# Power.net
KiCad netlist of a schematic drawn in Altium Designer
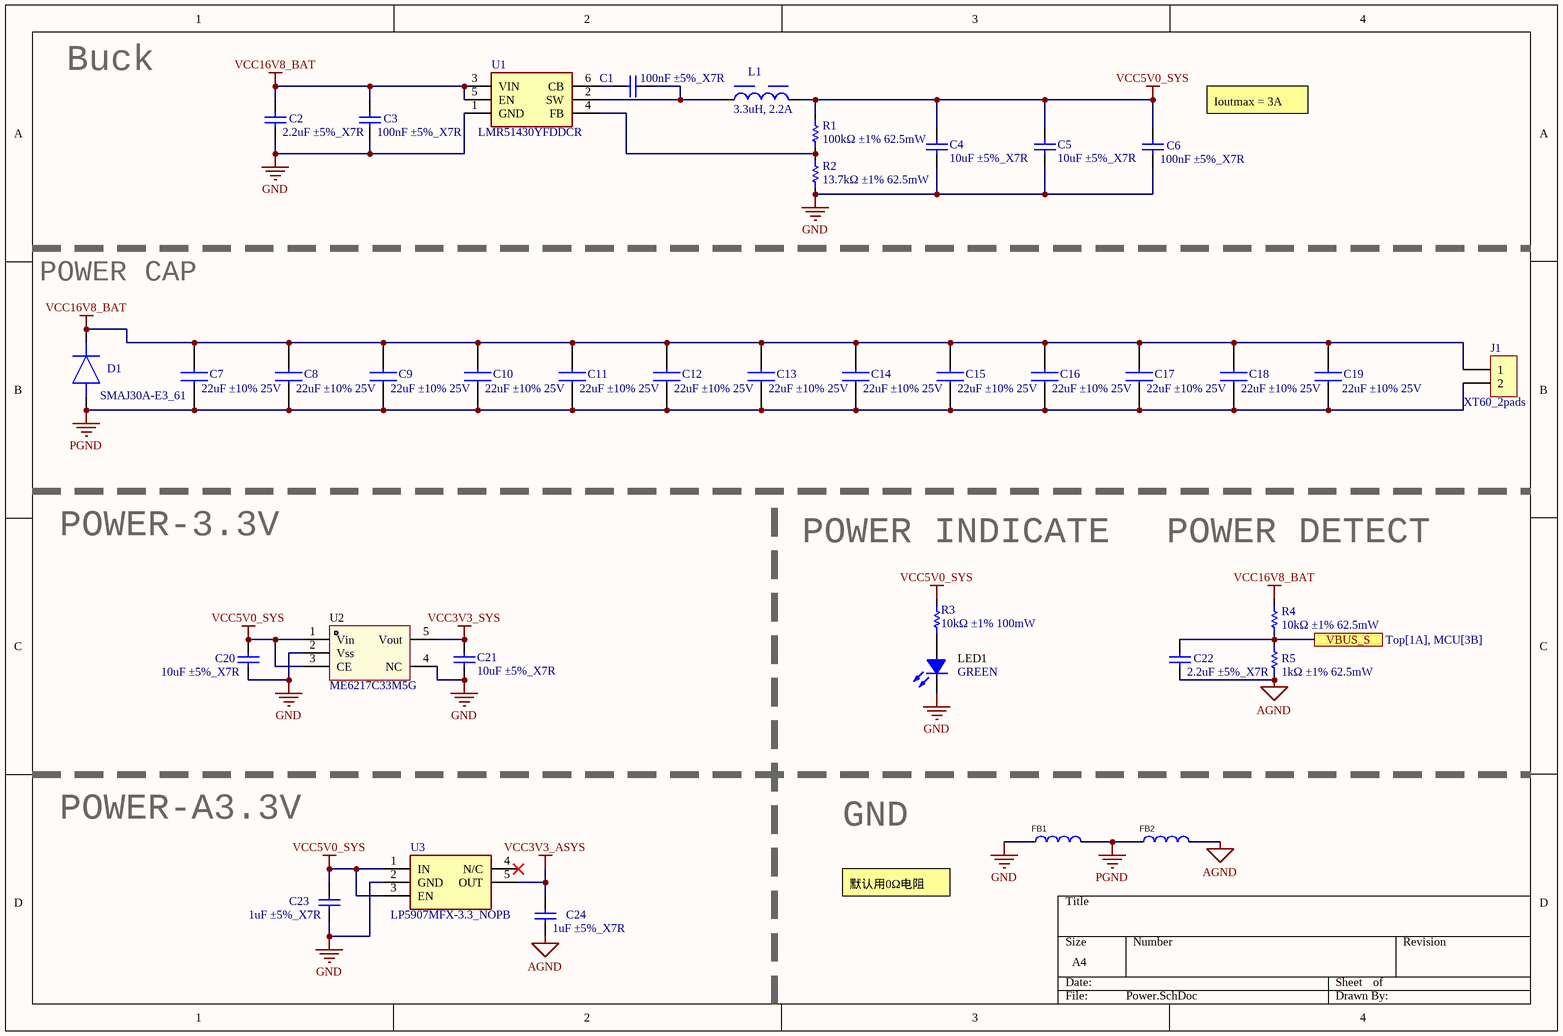
[diagram p0: Power.SchDoc]

(export (version "E")
  (design (tool "Eeschema 10.0.6"))
  (components
    (comp (ref "C1")
      (value "100nF ±5%_X7R")
      (footprint "C0402")
      (description "Capacitor")
      (fields (field (name "PUBLISHER") "Altium Limited"))
      (libsource (lib "Component") (part "Cap"))
    )
    (comp (ref "C2")
      (value "2.2uF ±5%_X7R")
      (footprint "C0603")
      (description "Capacitor")
      (fields (field (name "PUBLISHER") "Altium Limited"))
      (libsource (lib "Component") (part "Cap"))
    )
    (comp (ref "C3")
      (value "100nF ±5%_X7R")
      (footprint "C0402")
      (description "Capacitor")
      (fields (field (name "PUBLISHER") "Altium Limited"))
      (libsource (lib "Component") (part "Cap"))
    )
    (comp (ref "C4")
      (value "10uF ±5%_X7R")
      (footprint "C0603")
      (description "Capacitor")
      (fields (field (name "PUBLISHER") "Altium Limited"))
      (libsource (lib "Component") (part "Cap"))
    )
    (comp (ref "C5")
      (value "10uF ±5%_X7R")
      (footprint "C0603")
      (description "Capacitor")
      (fields (field (name "PUBLISHER") "Altium Limited"))
      (libsource (lib "Component") (part "Cap"))
    )
    (comp (ref "C6")
      (value "100nF ±5%_X7R")
      (footprint "C0402")
      (description "Capacitor")
      (fields (field (name "PUBLISHER") "Altium Limited"))
      (libsource (lib "Component") (part "Cap"))
    )
    (comp (ref "C7")
      (value "22uF ±10% 25V")
      (footprint "SamacSys:CAPC3225X270N")
      (description "Capacitor")
      (fields
        (field (name "MANUFACTURER_PART_NUMBER") "CL32A226KAJNNNE")
        (field (name "MOUSER PART NUMBER") "187-CL32A226KAJNNNE")
      )
      (libsource (lib "*") (part "CL32A226KAJNNNE"))
    )
    (comp (ref "C8")
      (value "22uF ±10% 25V")
      (footprint "SamacSys:CAPC3225X270N")
      (description "Capacitor")
      (fields
        (field (name "MANUFACTURER_PART_NUMBER") "CL32A226KAJNNNE")
        (field (name "MOUSER PART NUMBER") "187-CL32A226KAJNNNE")
      )
      (libsource (lib "*") (part "CL32A226KAJNNNE"))
    )
    (comp (ref "C9")
      (value "22uF ±10% 25V")
      (footprint "SamacSys:CAPC3225X270N")
      (description "Capacitor")
      (fields
        (field (name "MANUFACTURER_PART_NUMBER") "CL32A226KAJNNNE")
        (field (name "MOUSER PART NUMBER") "187-CL32A226KAJNNNE")
      )
      (libsource (lib "*") (part "CL32A226KAJNNNE"))
    )
    (comp (ref "C10")
      (value "22uF ±10% 25V")
      (footprint "SamacSys:CAPC3225X270N")
      (description "Capacitor")
      (fields
        (field (name "MANUFACTURER_PART_NUMBER") "CL32A226KAJNNNE")
        (field (name "MOUSER PART NUMBER") "187-CL32A226KAJNNNE")
      )
      (libsource (lib "*") (part "CL32A226KAJNNNE"))
    )
    (comp (ref "C11")
      (value "22uF ±10% 25V")
      (footprint "SamacSys:CAPC3225X270N")
      (description "Capacitor")
      (fields
        (field (name "MANUFACTURER_PART_NUMBER") "CL32A226KAJNNNE")
        (field (name "MOUSER PART NUMBER") "187-CL32A226KAJNNNE")
      )
      (libsource (lib "*") (part "CL32A226KAJNNNE"))
    )
    (comp (ref "C12")
      (value "22uF ±10% 25V")
      (footprint "SamacSys:CAPC3225X270N")
      (description "Capacitor")
      (fields
        (field (name "MANUFACTURER_PART_NUMBER") "CL32A226KAJNNNE")
        (field (name "MOUSER PART NUMBER") "187-CL32A226KAJNNNE")
      )
      (libsource (lib "*") (part "CL32A226KAJNNNE"))
    )
    (comp (ref "C13")
      (value "22uF ±10% 25V")
      (footprint "SamacSys:CAPC3225X270N")
      (description "Capacitor")
      (fields
        (field (name "MANUFACTURER_PART_NUMBER") "CL32A226KAJNNNE")
        (field (name "MOUSER PART NUMBER") "187-CL32A226KAJNNNE")
      )
      (libsource (lib "*") (part "CL32A226KAJNNNE"))
    )
    (comp (ref "C14")
      (value "22uF ±10% 25V")
      (footprint "CAPC3225X270N")
      (description "Capacitor")
      (fields
        (field (name "MANUFACTURER_PART_NUMBER") "CL32A226KAJNNNE")
        (field (name "MOUSER PART NUMBER") "187-CL32A226KAJNNNE")
      )
      (libsource (lib "*") (part "CL32A226KAJNNNE"))
    )
    (comp (ref "C15")
      (value "22uF ±10% 25V")
      (footprint "CAPC3225X270N")
      (description "Capacitor")
      (fields
        (field (name "MANUFACTURER_PART_NUMBER") "CL32A226KAJNNNE")
        (field (name "MOUSER PART NUMBER") "187-CL32A226KAJNNNE")
      )
      (libsource (lib "*") (part "CL32A226KAJNNNE"))
    )
    (comp (ref "C16")
      (value "22uF ±10% 25V")
      (footprint "CAPC3225X270N")
      (description "Capacitor")
      (fields
        (field (name "MANUFACTURER_PART_NUMBER") "CL32A226KAJNNNE")
        (field (name "MOUSER PART NUMBER") "187-CL32A226KAJNNNE")
      )
      (libsource (lib "*") (part "CL32A226KAJNNNE"))
    )
    (comp (ref "C17")
      (value "22uF ±10% 25V")
      (footprint "CAPC3225X270N")
      (description "Capacitor")
      (fields
        (field (name "MANUFACTURER_PART_NUMBER") "CL32A226KAJNNNE")
        (field (name "MOUSER PART NUMBER") "187-CL32A226KAJNNNE")
      )
      (libsource (lib "*") (part "CL32A226KAJNNNE"))
    )
    (comp (ref "C18")
      (value "22uF ±10% 25V")
      (footprint "CAPC3225X270N")
      (description "Capacitor")
      (fields
        (field (name "MANUFACTURER_PART_NUMBER") "CL32A226KAJNNNE")
        (field (name "MOUSER PART NUMBER") "187-CL32A226KAJNNNE")
      )
      (libsource (lib "*") (part "CL32A226KAJNNNE"))
    )
    (comp (ref "C19")
      (value "22uF ±10% 25V")
      (footprint "CAPC3225X270N")
      (description "Capacitor")
      (fields
        (field (name "MANUFACTURER_PART_NUMBER") "CL32A226KAJNNNE")
        (field (name "MOUSER PART NUMBER") "187-CL32A226KAJNNNE")
      )
      (libsource (lib "*") (part "CL32A226KAJNNNE"))
    )
    (comp (ref "C20")
      (value "10uF ±5%_X7R")
      (footprint "C0603")
      (description "Capacitor")
      (fields (field (name "PUBLISHER") "Altium Limited"))
      (libsource (lib "Component") (part "Cap"))
    )
    (comp (ref "C21")
      (value "10uF ±5%_X7R")
      (footprint "C0603")
      (description "Capacitor")
      (fields (field (name "PUBLISHER") "Altium Limited"))
      (libsource (lib "Component") (part "Cap"))
    )
    (comp (ref "C22")
      (value "2.2uF ±5%_X7R")
      (footprint "C0402")
      (description "Capacitor")
      (fields (field (name "PUBLISHER") "Altium Limited"))
      (libsource (lib "Component") (part "Cap"))
    )
    (comp (ref "C23")
      (value "1uF ±5%_X7R")
      (footprint "C0603")
      (description "Capacitor")
      (fields (field (name "PUBLISHER") "Altium Limited"))
      (libsource (lib "Component") (part "Cap"))
    )
    (comp (ref "C24")
      (value "1uF ±5%_X7R")
      (footprint "C0603")
      (description "Capacitor")
      (fields (field (name "PUBLISHER") "Altium Limited"))
      (libsource (lib "Component") (part "Cap"))
    )
    (comp (ref "D1")
      (value "SMAJ30A-E3_61")
      (footprint "SamacSys:DIOM5127X229N")
      (description "Diode")
      (fields
        (field (name "MANUFACTURER_PART_NUMBER") "SMAJ30A-E3/61")
        (field (name "MOUSER PART NUMBER") "625-SMAJ30A-E3")
      )
      (libsource (lib "*") (part "SMAJ30A-E3_61"))
    )
    (comp (ref "FB1")
      (value "?Ω@100MHz")
      (footprint "BEADC1608X75N")
      (description "MPZ1608S601ATA00")
      (fields (field (name "MANUFACTURER") "FH(风华)") (field (name "MANUFACTURER PART") "CBW321609U601T"))
      (libsource (lib "Component") (part "Ferrite Bead"))
    )
    (comp (ref "FB2")
      (value "?Ω@100MHz")
      (footprint "BEADC1608X75N")
      (description "MPZ1608S601ATA00")
      (fields (field (name "MANUFACTURER") "FH(风华)") (field (name "MANUFACTURER PART") "CBW321609U601T"))
      (libsource (lib "Component") (part "Ferrite Bead"))
    )
    (comp (ref "J1")
      (value "XT60_2pads")
      (footprint "XT60_2pads")
      (libsource (lib "Connectivity_Plugs") (part "XT60_2pads"))
    )
    (comp (ref "L1")
      (value "3.3uH, 2.2A")
      (footprint "WE-MAPI_3020")
      (description "WE-MAPI, size 3020, 3.3uH, 2.2A, 114mOhm")
      (fields
        (field (name "MANUFACTURER PART NUMBER") "74438336033")
        (field (name "MANUFACTURER") "Wurth Elektronik")
      )
      (libsource (lib "WE-MAPI (rev24b)") (part "74438336033"))
    )
    (comp (ref "LED1")
      (value "GREEN")
      (footprint "LED0603-RD")
      (fields
        (field (name "MANUFACTURER") "EVERLIGHT(亿光)")
        (field (name "MANUFACTURER PART") "17-21SURC/S530-A2/TR8")
      )
      (libsource (lib "Component") (part "LED"))
    )
    (comp (ref "R1")
      (value "100kΩ ±1% 62.5mW")
      (footprint "R0402")
      (description "Resistor")
      (fields (field (name "PUBLISHER") "Altium Limited"))
      (libsource (lib "Component") (part "Res"))
    )
    (comp (ref "R2")
      (value "13.7kΩ ±1% 62.5mW")
      (footprint "R0402")
      (description "Resistor")
      (fields (field (name "PUBLISHER") "Altium Limited"))
      (libsource (lib "Component") (part "Res"))
    )
    (comp (ref "R3")
      (value "10kΩ ±1% 100mW")
      (footprint "R0603")
      (description "Resistor")
      (fields (field (name "PUBLISHER") "Altium Limited"))
      (libsource (lib "Component") (part "Res"))
    )
    (comp (ref "R4")
      (value "10kΩ ±1% 62.5mW")
      (footprint "R0402")
      (description "Resistor")
      (fields (field (name "PUBLISHER") "Altium Limited"))
      (libsource (lib "Component") (part "Res"))
    )
    (comp (ref "R5")
      (value "1kΩ ±1% 62.5mW")
      (footprint "R0402")
      (description "Resistor")
      (fields (field (name "PUBLISHER") "Altium Limited"))
      (libsource (lib "Component") (part "Res"))
    )
    (comp (ref "U1")
      (value "LMR51430YFDDCR")
      (footprint "SamacSys:SOT95P280X110-6N")
      (description "Integrated Circuit")
      (fields (field (name "MOUSER PART NUMBER") "595-LMR51430YFDDCR"))
      (libsource (lib "SamacSys") (part "LMR51430YFDDCR"))
    )
    (comp (ref "U2")
      (value "ME6217C33M5G")
      (footprint "SOT-23-5_L3.0-W1.7-P0.95-LS2.8-BR")
      (fields (field (name "MANUFACTURER") "MICRONE(南京微盟)"))
      (libsource (lib "IC") (part "ME6217C33M5G"))
    )
    (comp (ref "U3")
      (value "LP5907MFX-3.3_NOPB")
      (footprint "SOT95P280X145-5N")
      (description "Integrated Circuit")
      (fields
        (field (name "MANUFACTURER_PART_NUMBER") "LP5907MFX-3.3/NOPB")
        (field (name "MOUSER PART NUMBER") "595-LP5907MFX-3.3NPB")
      )
      (libsource (lib "*") (part "LP5907MFX-3.3_NOPB"))
    )
  )
  (nets
    (net (code "1") (name "/VBUS_S") (class "Default")
      (node (ref "C22") (pin "2") (pinfunction "2_2") (pintype "passive"))
      (node (ref "R4") (pin "1") (pinfunction "1_1") (pintype "passive"))
      (node (ref "R5") (pin "2") (pinfunction "2_2") (pintype "passive"))
    )
    (net (code "2") (name "AGND") (class "Default")
      (node (ref "C22") (pin "1") (pinfunction "1_1") (pintype "passive"))
      (node (ref "C24") (pin "1") (pinfunction "1_1") (pintype "passive"))
      (node (ref "FB2") (pin "2") (pinfunction "2_2") (pintype "passive"))
      (node (ref "R5") (pin "1") (pinfunction "1_1") (pintype "passive"))
    )
    (net (code "3") (name "GND") (class "Default")
      (node (ref "C2") (pin "1") (pinfunction "1_1") (pintype "passive"))
      (node (ref "C20") (pin "1") (pinfunction "1_1") (pintype "passive"))
      (node (ref "C21") (pin "1") (pinfunction "1_1") (pintype "passive"))
      (node (ref "C23") (pin "1") (pinfunction "1_1") (pintype "passive"))
      (node (ref "C3") (pin "1") (pinfunction "1_1") (pintype "passive"))
      (node (ref "C4") (pin "1") (pinfunction "1_1") (pintype "passive"))
      (node (ref "C5") (pin "1") (pinfunction "1_1") (pintype "passive"))
      (node (ref "C6") (pin "1") (pinfunction "1_1") (pintype "passive"))
      (node (ref "FB1") (pin "1") (pinfunction "1_1") (pintype "passive"))
      (node (ref "LED1") (pin "2") (pinfunction "K_2") (pintype "passive"))
      (node (ref "R2") (pin "1") (pinfunction "1_1") (pintype "passive"))
      (node (ref "U1") (pin "1") (pinfunction "GND_1") (pintype "passive"))
      (node (ref "U2") (pin "2") (pinfunction "Vss_2") (pintype "passive"))
      (node (ref "U2") (pin "4") (pinfunction "NC_4") (pintype "passive"))
      (node (ref "U3") (pin "2") (pinfunction "GND_2") (pintype "passive"))
    )
    (net (code "4") (name "Net-(LED1-A)") (class "Default")
      (node (ref "LED1") (pin "1") (pinfunction "A_1") (pintype "passive"))
      (node (ref "R3") (pin "1") (pinfunction "1_1") (pintype "passive"))
    )
    (net (code "5") (name "Net-(U1-CB)") (class "Default")
      (node (ref "C1") (pin "2") (pinfunction "2_2") (pintype "passive"))
      (node (ref "U1") (pin "6") (pinfunction "CB_6") (pintype "passive"))
    )
    (net (code "6") (name "Net-(U1-FB)") (class "Default")
      (node (ref "R1") (pin "1") (pinfunction "1_1") (pintype "passive"))
      (node (ref "R2") (pin "2") (pinfunction "2_2") (pintype "passive"))
      (node (ref "U1") (pin "4") (pinfunction "FB_4") (pintype "passive"))
    )
    (net (code "7") (name "Net-(U1-SW)") (class "Default")
      (node (ref "C1") (pin "1") (pinfunction "1_1") (pintype "passive"))
      (node (ref "L1") (pin "1") (pinfunction "1_1") (pintype "passive"))
      (node (ref "U1") (pin "2") (pinfunction "SW_2") (pintype "passive"))
    )
    (net (code "8") (name "PGND") (class "Default")
      (node (ref "C10") (pin "1") (pinfunction "1_1") (pintype "passive"))
      (node (ref "C11") (pin "1") (pinfunction "1_1") (pintype "passive"))
      (node (ref "C12") (pin "1") (pinfunction "1_1") (pintype "passive"))
      (node (ref "C13") (pin "1") (pinfunction "1_1") (pintype "passive"))
      (node (ref "C14") (pin "1") (pinfunction "1_1") (pintype "passive"))
      (node (ref "C15") (pin "1") (pinfunction "1_1") (pintype "passive"))
      (node (ref "C16") (pin "1") (pinfunction "1_1") (pintype "passive"))
      (node (ref "C17") (pin "1") (pinfunction "1_1") (pintype "passive"))
      (node (ref "C18") (pin "1") (pinfunction "1_1") (pintype "passive"))
      (node (ref "C19") (pin "1") (pinfunction "1_1") (pintype "passive"))
      (node (ref "C7") (pin "1") (pinfunction "1_1") (pintype "passive"))
      (node (ref "C8") (pin "1") (pinfunction "1_1") (pintype "passive"))
      (node (ref "C9") (pin "1") (pinfunction "1_1") (pintype "passive"))
      (node (ref "D1") (pin "2") (pinfunction "A_2") (pintype "passive"))
      (node (ref "FB1") (pin "2") (pinfunction "2_2") (pintype "passive"))
      (node (ref "FB2") (pin "1") (pinfunction "1_1") (pintype "passive"))
      (node (ref "J1") (pin "2") (pinfunction "2_2") (pintype "passive"))
    )
    (net (code "9") (name "VCC3V3_ASYS") (class "Default")
      (node (ref "C24") (pin "2") (pinfunction "2_2") (pintype "passive"))
      (node (ref "U3") (pin "5") (pinfunction "OUT_5") (pintype "passive"))
    )
    (net (code "10") (name "VCC3V3_SYS") (class "Default")
      (node (ref "C21") (pin "2") (pinfunction "2_2") (pintype "passive"))
      (node (ref "U2") (pin "5") (pinfunction "Vout_5") (pintype "passive"))
    )
    (net (code "11") (name "VCC5V0_SYS") (class "Default")
      (node (ref "C20") (pin "2") (pinfunction "2_2") (pintype "passive"))
      (node (ref "C23") (pin "2") (pinfunction "2_2") (pintype "passive"))
      (node (ref "C4") (pin "2") (pinfunction "2_2") (pintype "passive"))
      (node (ref "C5") (pin "2") (pinfunction "2_2") (pintype "passive"))
      (node (ref "C6") (pin "2") (pinfunction "2_2") (pintype "passive"))
      (node (ref "L1") (pin "2") (pinfunction "2_2") (pintype "passive"))
      (node (ref "R1") (pin "2") (pinfunction "2_2") (pintype "passive"))
      (node (ref "R3") (pin "2") (pinfunction "2_2") (pintype "passive"))
      (node (ref "U2") (pin "1") (pinfunction "Vin_1") (pintype "passive"))
      (node (ref "U2") (pin "3") (pinfunction "CE_3") (pintype "passive"))
      (node (ref "U3") (pin "1") (pinfunction "IN_1") (pintype "passive"))
      (node (ref "U3") (pin "3") (pinfunction "EN_3") (pintype "passive"))
    )
    (net (code "12") (name "VCC16V8_BAT") (class "Default")
      (node (ref "C10") (pin "2") (pinfunction "2_2") (pintype "passive"))
      (node (ref "C11") (pin "2") (pinfunction "2_2") (pintype "passive"))
      (node (ref "C12") (pin "2") (pinfunction "2_2") (pintype "passive"))
      (node (ref "C13") (pin "2") (pinfunction "2_2") (pintype "passive"))
      (node (ref "C14") (pin "2") (pinfunction "2_2") (pintype "passive"))
      (node (ref "C15") (pin "2") (pinfunction "2_2") (pintype "passive"))
      (node (ref "C16") (pin "2") (pinfunction "2_2") (pintype "passive"))
      (node (ref "C17") (pin "2") (pinfunction "2_2") (pintype "passive"))
      (node (ref "C18") (pin "2") (pinfunction "2_2") (pintype "passive"))
      (node (ref "C19") (pin "2") (pinfunction "2_2") (pintype "passive"))
      (node (ref "C2") (pin "2") (pinfunction "2_2") (pintype "passive"))
      (node (ref "C3") (pin "2") (pinfunction "2_2") (pintype "passive"))
      (node (ref "C7") (pin "2") (pinfunction "2_2") (pintype "passive"))
      (node (ref "C8") (pin "2") (pinfunction "2_2") (pintype "passive"))
      (node (ref "C9") (pin "2") (pinfunction "2_2") (pintype "passive"))
      (node (ref "D1") (pin "1") (pinfunction "K_1") (pintype "passive"))
      (node (ref "J1") (pin "1") (pinfunction "1_1") (pintype "passive"))
      (node (ref "R4") (pin "2") (pinfunction "2_2") (pintype "passive"))
      (node (ref "U1") (pin "3") (pinfunction "VIN_3") (pintype "passive"))
      (node (ref "U1") (pin "5") (pinfunction "EN_5") (pintype "passive"))
    )
    (net (code "13") (name "unconnected-(U3-N{slash}C-Pad4)") (class "Default")
      (node (ref "U3") (pin "4") (pinfunction "N/C_4") (pintype "passive+no_connect"))
    )
  )
)
